# Conn_A.net
KiCad netlist of a schematic drawn in Altium Designer
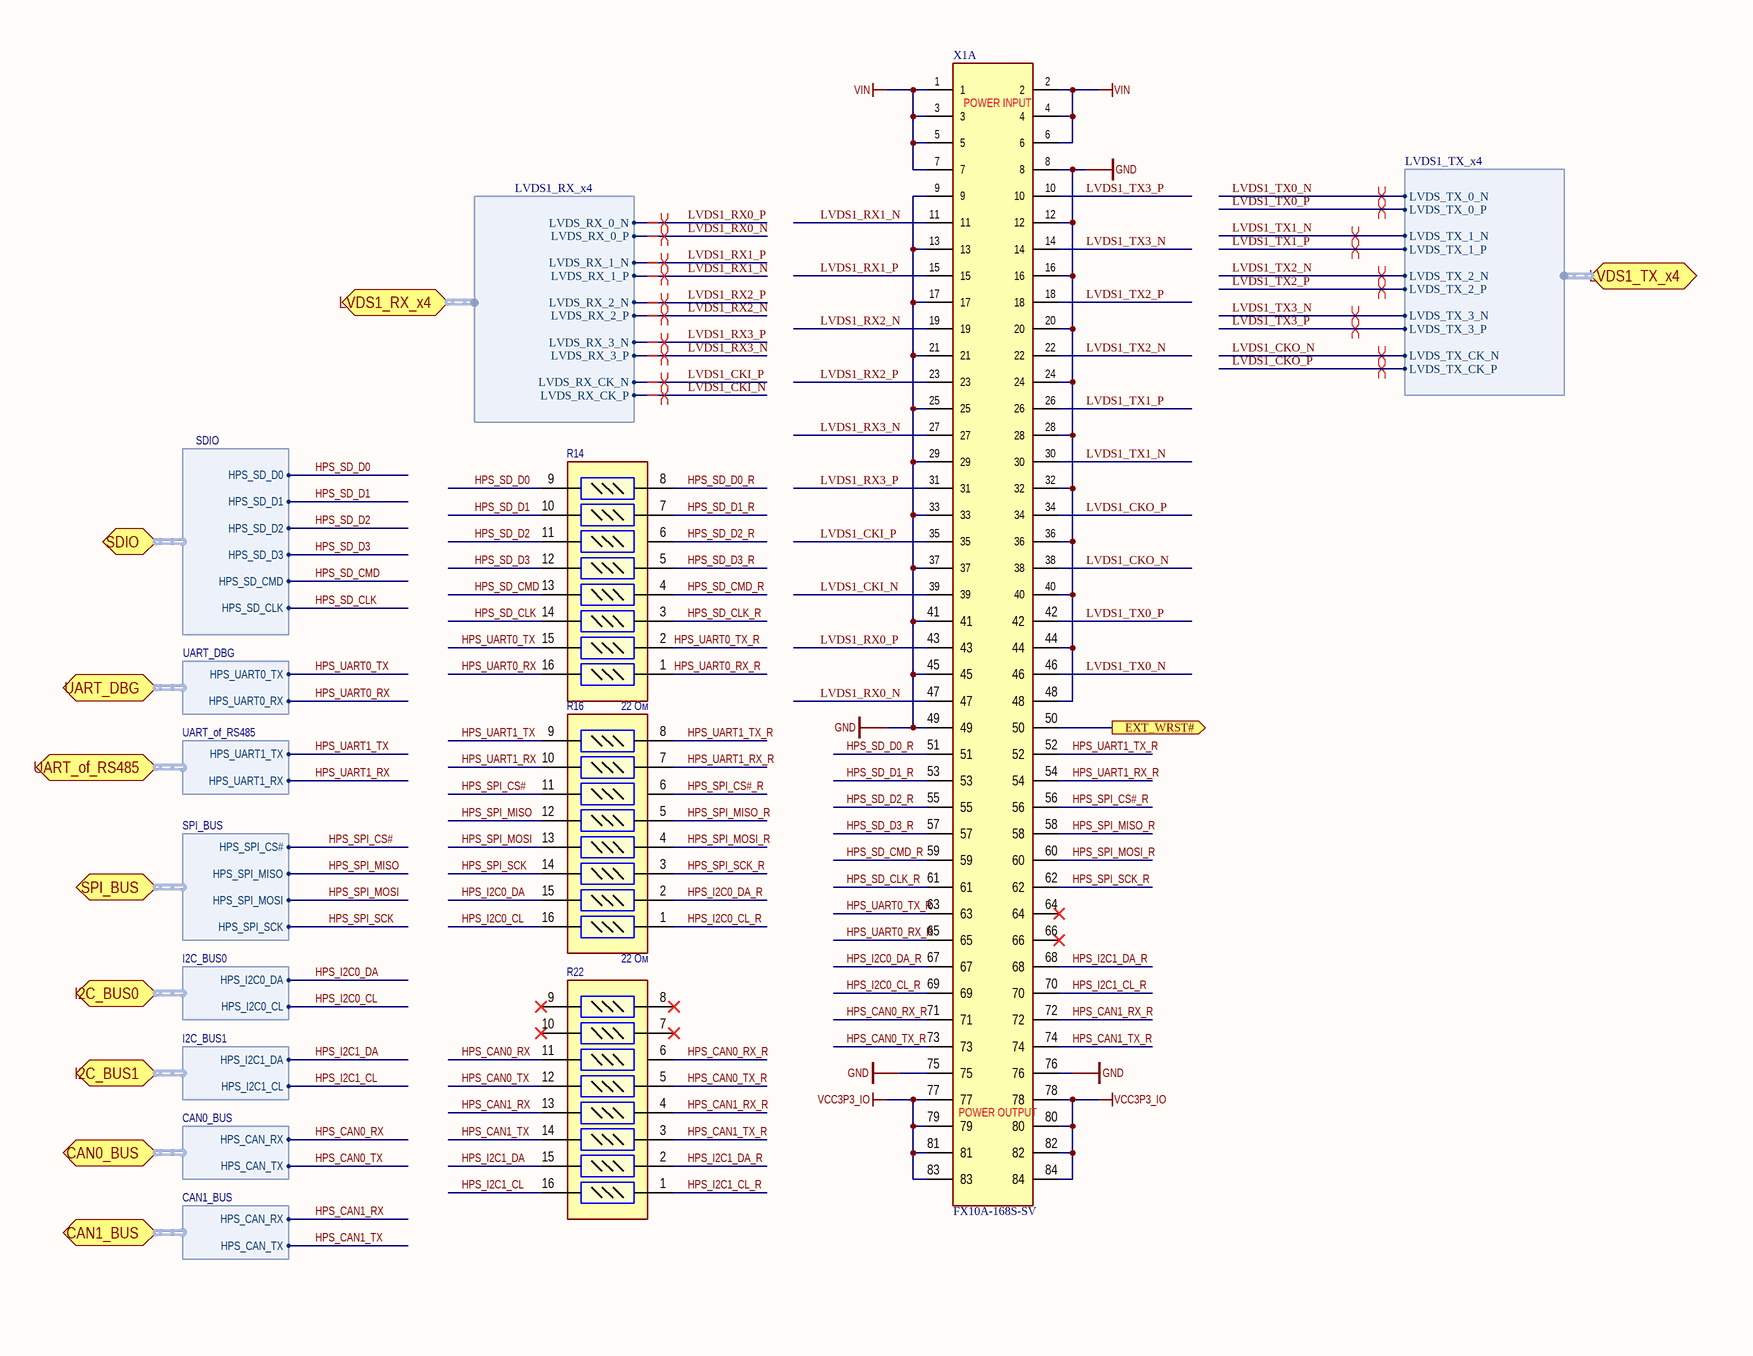
[diagram p0: Conn_A.SchDoc, left]
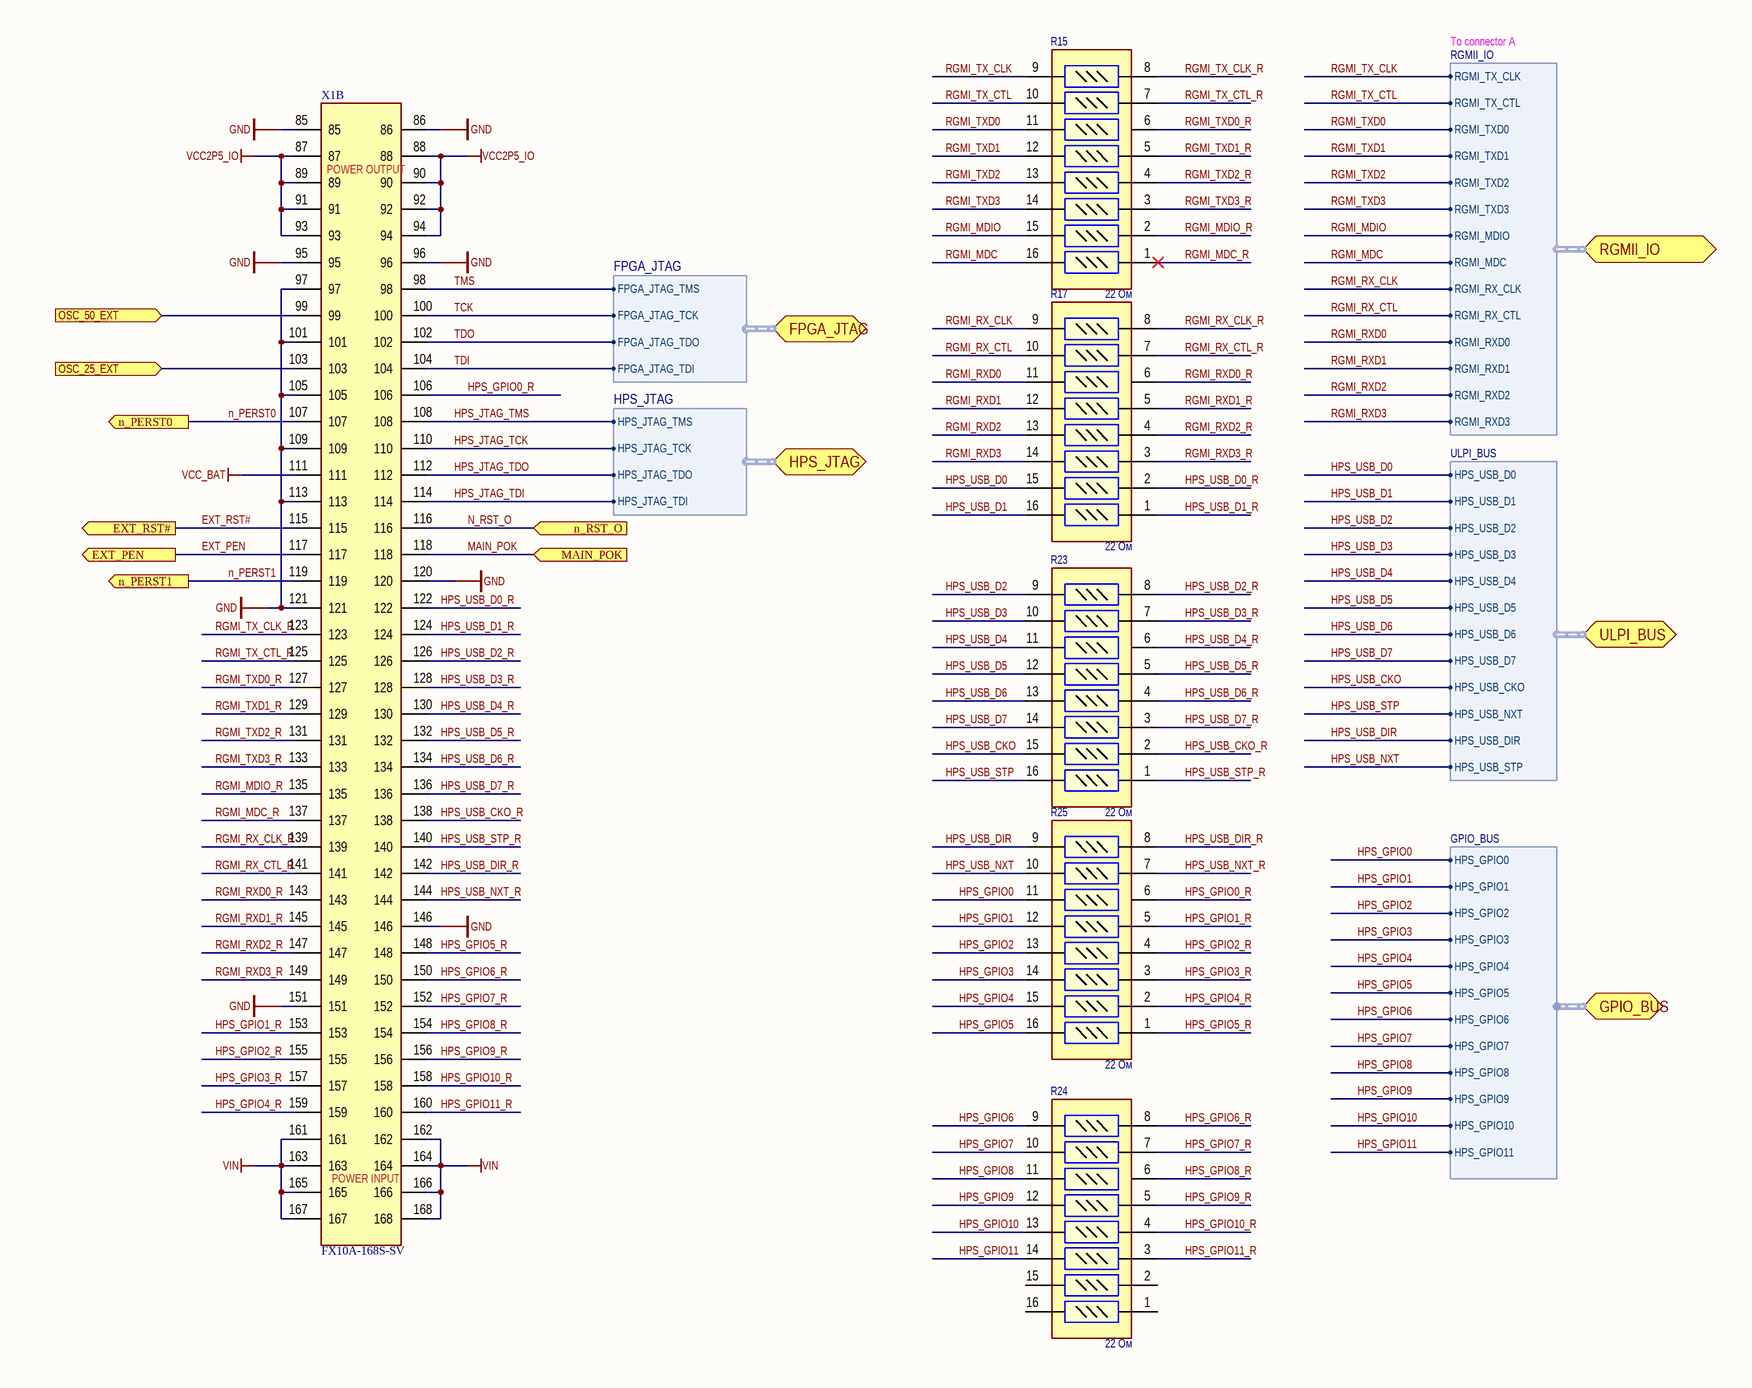
[diagram p1: Conn_A.SchDoc, right]

(export (version "E")
  (design (tool "Eeschema 10.0.6"))
  (components
    (comp (ref "R14")
      (value "22 Ом")
      (footprint "CAT16-J8")
      (description "Набор чип резисторов")
      (fields (field (name "Comment") "YC248-JR-07-22 Ом"))
      (libsource (lib "SD_IC") (part "YC248-JR-07-#"))
    )
    (comp (ref "R15")
      (value "22 Ом")
      (footprint "CAT16-J8")
      (description "Набор чип резисторов")
      (fields (field (name "Comment") "YC248-JR-07-22 Ом"))
      (libsource (lib "SD_IC") (part "YC248-JR-07-#"))
    )
    (comp (ref "R16")
      (value "22 Ом")
      (footprint "CAT16-J8")
      (description "Набор чип резисторов")
      (fields (field (name "Comment") "YC248-JR-07-22 Ом"))
      (libsource (lib "SD_IC") (part "YC248-JR-07-#"))
    )
    (comp (ref "R17")
      (value "22 Ом")
      (footprint "CAT16-J8")
      (description "Набор чип резисторов")
      (fields (field (name "Comment") "YC248-JR-07-22 Ом"))
      (libsource (lib "SD_IC") (part "YC248-JR-07-#"))
    )
    (comp (ref "R22")
      (value "YC248-JR-07-")
      (footprint "CAT16-J8")
      (description "Набор чип резисторов")
      (libsource (lib "SD_IC") (part "YC248-JR-07-#"))
    )
    (comp (ref "R23")
      (value "22 Ом")
      (footprint "CAT16-J8")
      (description "Набор чип резисторов")
      (fields (field (name "Comment") "YC248-JR-07-22 Ом"))
      (libsource (lib "SD_IC") (part "YC248-JR-07-#"))
    )
    (comp (ref "R24")
      (value "22 Ом")
      (footprint "CAT16-J8")
      (description "Набор чип резисторов")
      (fields (field (name "Comment") "YC248-JR-07-22 Ом"))
      (libsource (lib "SD_IC") (part "YC248-JR-07-#"))
    )
    (comp (ref "R25")
      (value "22 Ом")
      (footprint "CAT16-J8")
      (description "Набор чип резисторов")
      (fields (field (name "Comment") "YC248-JR-07-22 Ом"))
      (libsource (lib "SD_IC") (part "YC248-JR-07-#"))
    )
    (comp (ref "X1")
      (value "FX10A-168S-SV")
      (footprint "FX10A-168S-SV")
      (libsource (lib "SD_IC") (part "FX10A-168S-SV"))
    )
  )
  (nets
    (net (code "16") (name "/EXT_PEN") (class "Default")
      (node (ref "X1") (pin "117") (pinfunction "117_117") (pintype "passive"))
    )
    (net (code "17") (name "/EXT_RST#") (class "Default")
      (node (ref "X1") (pin "115") (pinfunction "115_115") (pintype "passive"))
    )
    (net (code "18") (name "/EXT_WRST#") (class "Default")
      (node (ref "X1") (pin "50") (pinfunction "50_50") (pintype "passive"))
    )
    (net (code "19") (name "/HPS_CAN0_RX") (class "Default")
      (node (ref "R22") (pin "11") (pintype "passive"))
    )
    (net (code "20") (name "/HPS_CAN0_RX_R") (class "Default")
      (node (ref "R22") (pin "6") (pintype "passive"))
      (node (ref "X1") (pin "71") (pinfunction "71_71") (pintype "passive"))
    )
    (net (code "21") (name "/HPS_CAN0_TX") (class "Default")
      (node (ref "R22") (pin "12") (pintype "passive"))
    )
    (net (code "22") (name "/HPS_CAN0_TX_R") (class "Default")
      (node (ref "R22") (pin "5") (pintype "passive"))
      (node (ref "X1") (pin "73") (pinfunction "73_73") (pintype "passive"))
    )
    (net (code "23") (name "/HPS_CAN1_RX") (class "Default")
      (node (ref "R22") (pin "13") (pintype "passive"))
    )
    (net (code "24") (name "/HPS_CAN1_RX_R") (class "Default")
      (node (ref "R22") (pin "4") (pintype "passive"))
      (node (ref "X1") (pin "72") (pinfunction "72_72") (pintype "passive"))
    )
    (net (code "25") (name "/HPS_CAN1_TX") (class "Default")
      (node (ref "R22") (pin "14") (pintype "passive"))
    )
    (net (code "26") (name "/HPS_CAN1_TX_R") (class "Default")
      (node (ref "R22") (pin "3") (pintype "passive"))
      (node (ref "X1") (pin "74") (pinfunction "74_74") (pintype "passive"))
    )
    (net (code "27") (name "/HPS_GPIO0") (class "Default") (node (ref "R25") (pin "11") (pintype "passive")))
    (net (code "28") (name "/HPS_GPIO0_R") (class "Default")
      (node (ref "R25") (pin "6") (pintype "passive"))
      (node (ref "X1") (pin "106") (pinfunction "106_106") (pintype "passive"))
    )
    (net (code "29") (name "/HPS_GPIO1") (class "Default") (node (ref "R25") (pin "12") (pintype "passive")))
    (net (code "30") (name "/HPS_GPIO1_R") (class "Default")
      (node (ref "R25") (pin "5") (pintype "passive"))
      (node (ref "X1") (pin "153") (pinfunction "153_153") (pintype "passive"))
    )
    (net (code "31") (name "/HPS_GPIO2") (class "Default") (node (ref "R25") (pin "13") (pintype "passive")))
    (net (code "32") (name "/HPS_GPIO2_R") (class "Default")
      (node (ref "R25") (pin "4") (pintype "passive"))
      (node (ref "X1") (pin "155") (pinfunction "155_155") (pintype "passive"))
    )
    (net (code "33") (name "/HPS_GPIO3") (class "Default") (node (ref "R25") (pin "14") (pintype "passive")))
    (net (code "34") (name "/HPS_GPIO3_R") (class "Default")
      (node (ref "R25") (pin "3") (pintype "passive"))
      (node (ref "X1") (pin "157") (pinfunction "157_157") (pintype "passive"))
    )
    (net (code "35") (name "/HPS_GPIO4") (class "Default") (node (ref "R25") (pin "15") (pintype "passive")))
    (net (code "36") (name "/HPS_GPIO4_R") (class "Default")
      (node (ref "R25") (pin "2") (pintype "passive"))
      (node (ref "X1") (pin "159") (pinfunction "159_159") (pintype "passive"))
    )
    (net (code "37") (name "/HPS_GPIO5") (class "Default") (node (ref "R25") (pin "16") (pintype "passive")))
    (net (code "38") (name "/HPS_GPIO5_R") (class "Default")
      (node (ref "R25") (pin "1") (pintype "passive"))
      (node (ref "X1") (pin "148") (pinfunction "148_148") (pintype "passive"))
    )
    (net (code "39") (name "/HPS_GPIO6") (class "Default") (node (ref "R24") (pin "9") (pintype "passive")))
    (net (code "40") (name "/HPS_GPIO6_R") (class "Default")
      (node (ref "R24") (pin "8") (pintype "passive"))
      (node (ref "X1") (pin "150") (pinfunction "150_150") (pintype "passive"))
    )
    (net (code "41") (name "/HPS_GPIO7") (class "Default") (node (ref "R24") (pin "10") (pintype "passive")))
    (net (code "42") (name "/HPS_GPIO7_R") (class "Default")
      (node (ref "R24") (pin "7") (pintype "passive"))
      (node (ref "X1") (pin "152") (pinfunction "152_152") (pintype "passive"))
    )
    (net (code "43") (name "/HPS_GPIO8") (class "Default") (node (ref "R24") (pin "11") (pintype "passive")))
    (net (code "44") (name "/HPS_GPIO8_R") (class "Default")
      (node (ref "R24") (pin "6") (pintype "passive"))
      (node (ref "X1") (pin "154") (pinfunction "154_154") (pintype "passive"))
    )
    (net (code "45") (name "/HPS_GPIO9") (class "Default") (node (ref "R24") (pin "12") (pintype "passive")))
    (net (code "46") (name "/HPS_GPIO9_R") (class "Default")
      (node (ref "R24") (pin "5") (pintype "passive"))
      (node (ref "X1") (pin "156") (pinfunction "156_156") (pintype "passive"))
    )
    (net (code "47") (name "/HPS_GPIO10") (class "Default") (node (ref "R24") (pin "13") (pintype "passive")))
    (net (code "48") (name "/HPS_GPIO10_R") (class "Default")
      (node (ref "R24") (pin "4") (pintype "passive"))
      (node (ref "X1") (pin "158") (pinfunction "158_158") (pintype "passive"))
    )
    (net (code "49") (name "/HPS_GPIO11") (class "Default") (node (ref "R24") (pin "14") (pintype "passive")))
    (net (code "50") (name "/HPS_GPIO11_R") (class "Default")
      (node (ref "R24") (pin "3") (pintype "passive"))
      (node (ref "X1") (pin "160") (pinfunction "160_160") (pintype "passive"))
    )
    (net (code "51") (name "/HPS_I2C0_CL") (class "Default")
      (node (ref "R16") (pin "16") (pintype "passive"))
    )
    (net (code "52") (name "/HPS_I2C0_CL_R") (class "Default")
      (node (ref "R16") (pin "1") (pintype "passive"))
      (node (ref "X1") (pin "69") (pinfunction "69_69") (pintype "passive"))
    )
    (net (code "53") (name "/HPS_I2C0_DA") (class "Default")
      (node (ref "R16") (pin "15") (pintype "passive"))
    )
    (net (code "54") (name "/HPS_I2C0_DA_R") (class "Default")
      (node (ref "R16") (pin "2") (pintype "passive"))
      (node (ref "X1") (pin "67") (pinfunction "67_67") (pintype "passive"))
    )
    (net (code "55") (name "/HPS_I2C1_CL") (class "Default")
      (node (ref "R22") (pin "16") (pintype "passive"))
    )
    (net (code "56") (name "/HPS_I2C1_CL_R") (class "Default")
      (node (ref "R22") (pin "1") (pintype "passive"))
      (node (ref "X1") (pin "70") (pinfunction "70_70") (pintype "passive"))
    )
    (net (code "57") (name "/HPS_I2C1_DA") (class "Default")
      (node (ref "R22") (pin "15") (pintype "passive"))
    )
    (net (code "58") (name "/HPS_I2C1_DA_R") (class "Default")
      (node (ref "R22") (pin "2") (pintype "passive"))
      (node (ref "X1") (pin "68") (pinfunction "68_68") (pintype "passive"))
    )
    (net (code "59") (name "/HPS_JTAG_TCK") (class "Default")
      (node (ref "X1") (pin "110") (pinfunction "110_110") (pintype "passive"))
    )
    (net (code "60") (name "/HPS_JTAG_TDI") (class "Default")
      (node (ref "X1") (pin "114") (pinfunction "114_114") (pintype "passive"))
    )
    (net (code "61") (name "/HPS_JTAG_TDO") (class "Default")
      (node (ref "X1") (pin "112") (pinfunction "112_112") (pintype "passive"))
    )
    (net (code "62") (name "/HPS_JTAG_TMS") (class "Default")
      (node (ref "X1") (pin "108") (pinfunction "108_108") (pintype "passive"))
    )
    (net (code "63") (name "/HPS_SD_CLK") (class "Default") (node (ref "R14") (pin "14") (pintype "passive")))
    (net (code "64") (name "/HPS_SD_CLK_R") (class "Default")
      (node (ref "R14") (pin "3") (pintype "passive"))
      (node (ref "X1") (pin "61") (pinfunction "61_61") (pintype "passive"))
    )
    (net (code "65") (name "/HPS_SD_CMD") (class "Default") (node (ref "R14") (pin "13") (pintype "passive")))
    (net (code "66") (name "/HPS_SD_CMD_R") (class "Default")
      (node (ref "R14") (pin "4") (pintype "passive"))
      (node (ref "X1") (pin "59") (pinfunction "59_59") (pintype "passive"))
    )
    (net (code "67") (name "/HPS_SD_D0") (class "Default") (node (ref "R14") (pin "9") (pintype "passive")))
    (net (code "68") (name "/HPS_SD_D0_R") (class "Default")
      (node (ref "R14") (pin "8") (pintype "passive"))
      (node (ref "X1") (pin "51") (pinfunction "51_51") (pintype "passive"))
    )
    (net (code "69") (name "/HPS_SD_D1") (class "Default") (node (ref "R14") (pin "10") (pintype "passive")))
    (net (code "70") (name "/HPS_SD_D1_R") (class "Default")
      (node (ref "R14") (pin "7") (pintype "passive"))
      (node (ref "X1") (pin "53") (pinfunction "53_53") (pintype "passive"))
    )
    (net (code "71") (name "/HPS_SD_D2") (class "Default") (node (ref "R14") (pin "11") (pintype "passive")))
    (net (code "72") (name "/HPS_SD_D2_R") (class "Default")
      (node (ref "R14") (pin "6") (pintype "passive"))
      (node (ref "X1") (pin "55") (pinfunction "55_55") (pintype "passive"))
    )
    (net (code "73") (name "/HPS_SD_D3") (class "Default") (node (ref "R14") (pin "12") (pintype "passive")))
    (net (code "74") (name "/HPS_SD_D3_R") (class "Default")
      (node (ref "R14") (pin "5") (pintype "passive"))
      (node (ref "X1") (pin "57") (pinfunction "57_57") (pintype "passive"))
    )
    (net (code "75") (name "/HPS_SPI_CS#") (class "Default")
      (node (ref "R16") (pin "11") (pintype "passive"))
    )
    (net (code "76") (name "/HPS_SPI_CS#_R") (class "Default")
      (node (ref "R16") (pin "6") (pintype "passive"))
      (node (ref "X1") (pin "56") (pinfunction "56_56") (pintype "passive"))
    )
    (net (code "77") (name "/HPS_SPI_MISO") (class "Default")
      (node (ref "R16") (pin "12") (pintype "passive"))
    )
    (net (code "78") (name "/HPS_SPI_MISO_R") (class "Default")
      (node (ref "R16") (pin "5") (pintype "passive"))
      (node (ref "X1") (pin "58") (pinfunction "58_58") (pintype "passive"))
    )
    (net (code "79") (name "/HPS_SPI_MOSI") (class "Default")
      (node (ref "R16") (pin "13") (pintype "passive"))
    )
    (net (code "80") (name "/HPS_SPI_MOSI_R") (class "Default")
      (node (ref "R16") (pin "4") (pintype "passive"))
      (node (ref "X1") (pin "60") (pinfunction "60_60") (pintype "passive"))
    )
    (net (code "81") (name "/HPS_SPI_SCK") (class "Default")
      (node (ref "R16") (pin "14") (pintype "passive"))
    )
    (net (code "82") (name "/HPS_SPI_SCK_R") (class "Default")
      (node (ref "R16") (pin "3") (pintype "passive"))
      (node (ref "X1") (pin "62") (pinfunction "62_62") (pintype "passive"))
    )
    (net (code "83") (name "/HPS_UART0_RX") (class "Default")
      (node (ref "R14") (pin "16") (pintype "passive"))
    )
    (net (code "84") (name "/HPS_UART0_RX_R") (class "Default")
      (node (ref "R14") (pin "1") (pintype "passive"))
      (node (ref "X1") (pin "65") (pinfunction "65_65") (pintype "passive"))
    )
    (net (code "85") (name "/HPS_UART0_TX") (class "Default")
      (node (ref "R14") (pin "15") (pintype "passive"))
    )
    (net (code "86") (name "/HPS_UART0_TX_R") (class "Default")
      (node (ref "R14") (pin "2") (pintype "passive"))
      (node (ref "X1") (pin "63") (pinfunction "63_63") (pintype "passive"))
    )
    (net (code "87") (name "/HPS_UART1_RX") (class "Default")
      (node (ref "R16") (pin "10") (pintype "passive"))
    )
    (net (code "88") (name "/HPS_UART1_RX_R") (class "Default")
      (node (ref "R16") (pin "7") (pintype "passive"))
      (node (ref "X1") (pin "54") (pinfunction "54_54") (pintype "passive"))
    )
    (net (code "89") (name "/HPS_UART1_TX") (class "Default")
      (node (ref "R16") (pin "9") (pintype "passive"))
    )
    (net (code "90") (name "/HPS_UART1_TX_R") (class "Default")
      (node (ref "R16") (pin "8") (pintype "passive"))
      (node (ref "X1") (pin "52") (pinfunction "52_52") (pintype "passive"))
    )
    (net (code "91") (name "/HPS_USB_CKO") (class "Default")
      (node (ref "R23") (pin "15") (pintype "passive"))
    )
    (net (code "92") (name "/HPS_USB_CKO_R") (class "Default")
      (node (ref "R23") (pin "2") (pintype "passive"))
      (node (ref "X1") (pin "138") (pinfunction "138_138") (pintype "passive"))
    )
    (net (code "93") (name "/HPS_USB_D0") (class "Default") (node (ref "R17") (pin "15") (pintype "passive")))
    (net (code "94") (name "/HPS_USB_D0_R") (class "Default")
      (node (ref "R17") (pin "2") (pintype "passive"))
      (node (ref "X1") (pin "122") (pinfunction "122_122") (pintype "passive"))
    )
    (net (code "95") (name "/HPS_USB_D1") (class "Default") (node (ref "R17") (pin "16") (pintype "passive")))
    (net (code "96") (name "/HPS_USB_D1_R") (class "Default")
      (node (ref "R17") (pin "1") (pintype "passive"))
      (node (ref "X1") (pin "124") (pinfunction "124_124") (pintype "passive"))
    )
    (net (code "97") (name "/HPS_USB_D2") (class "Default") (node (ref "R23") (pin "9") (pintype "passive")))
    (net (code "98") (name "/HPS_USB_D2_R") (class "Default")
      (node (ref "R23") (pin "8") (pintype "passive"))
      (node (ref "X1") (pin "126") (pinfunction "126_126") (pintype "passive"))
    )
    (net (code "99") (name "/HPS_USB_D3") (class "Default") (node (ref "R23") (pin "10") (pintype "passive")))
    (net (code "100") (name "/HPS_USB_D3_R") (class "Default")
      (node (ref "R23") (pin "7") (pintype "passive"))
      (node (ref "X1") (pin "128") (pinfunction "128_128") (pintype "passive"))
    )
    (net (code "101") (name "/HPS_USB_D4") (class "Default")
      (node (ref "R23") (pin "11") (pintype "passive"))
    )
    (net (code "102") (name "/HPS_USB_D4_R") (class "Default")
      (node (ref "R23") (pin "6") (pintype "passive"))
      (node (ref "X1") (pin "130") (pinfunction "130_130") (pintype "passive"))
    )
    (net (code "103") (name "/HPS_USB_D5") (class "Default")
      (node (ref "R23") (pin "12") (pintype "passive"))
    )
    (net (code "104") (name "/HPS_USB_D5_R") (class "Default")
      (node (ref "R23") (pin "5") (pintype "passive"))
      (node (ref "X1") (pin "132") (pinfunction "132_132") (pintype "passive"))
    )
    (net (code "105") (name "/HPS_USB_D6") (class "Default")
      (node (ref "R23") (pin "13") (pintype "passive"))
    )
    (net (code "106") (name "/HPS_USB_D6_R") (class "Default")
      (node (ref "R23") (pin "4") (pintype "passive"))
      (node (ref "X1") (pin "134") (pinfunction "134_134") (pintype "passive"))
    )
    (net (code "107") (name "/HPS_USB_D7") (class "Default")
      (node (ref "R23") (pin "14") (pintype "passive"))
    )
    (net (code "108") (name "/HPS_USB_D7_R") (class "Default")
      (node (ref "R23") (pin "3") (pintype "passive"))
      (node (ref "X1") (pin "136") (pinfunction "136_136") (pintype "passive"))
    )
    (net (code "109") (name "/HPS_USB_DIR") (class "Default")
      (node (ref "R25") (pin "9") (pintype "passive"))
    )
    (net (code "110") (name "/HPS_USB_DIR_R") (class "Default")
      (node (ref "R25") (pin "8") (pintype "passive"))
      (node (ref "X1") (pin "142") (pinfunction "142_142") (pintype "passive"))
    )
    (net (code "111") (name "/HPS_USB_NXT") (class "Default")
      (node (ref "R25") (pin "10") (pintype "passive"))
    )
    (net (code "112") (name "/HPS_USB_NXT_R") (class "Default")
      (node (ref "R25") (pin "7") (pintype "passive"))
      (node (ref "X1") (pin "144") (pinfunction "144_144") (pintype "passive"))
    )
    (net (code "113") (name "/HPS_USB_STP") (class "Default")
      (node (ref "R23") (pin "16") (pintype "passive"))
    )
    (net (code "114") (name "/HPS_USB_STP_R") (class "Default")
      (node (ref "R23") (pin "1") (pintype "passive"))
      (node (ref "X1") (pin "140") (pinfunction "140_140") (pintype "passive"))
    )
    (net (code "115") (name "/LVDS1_CKI_N") (class "Default")
      (node (ref "X1") (pin "39") (pinfunction "39_39") (pintype "passive"))
    )
    (net (code "116") (name "/LVDS1_CKI_P") (class "Default")
      (node (ref "X1") (pin "35") (pinfunction "35_35") (pintype "passive"))
    )
    (net (code "117") (name "/LVDS1_CKO_N") (class "Default")
      (node (ref "X1") (pin "38") (pinfunction "38_38") (pintype "passive"))
    )
    (net (code "118") (name "/LVDS1_CKO_P") (class "Default")
      (node (ref "X1") (pin "34") (pinfunction "34_34") (pintype "passive"))
    )
    (net (code "119") (name "/LVDS1_RX0_N") (class "Default")
      (node (ref "X1") (pin "47") (pinfunction "47_47") (pintype "passive"))
    )
    (net (code "120") (name "/LVDS1_RX0_P") (class "Default")
      (node (ref "X1") (pin "43") (pinfunction "43_43") (pintype "passive"))
    )
    (net (code "121") (name "/LVDS1_RX1_N") (class "Default")
      (node (ref "X1") (pin "11") (pinfunction "11_11") (pintype "passive"))
    )
    (net (code "122") (name "/LVDS1_RX1_P") (class "Default")
      (node (ref "X1") (pin "15") (pinfunction "15_15") (pintype "passive"))
    )
    (net (code "123") (name "/LVDS1_RX2_N") (class "Default")
      (node (ref "X1") (pin "19") (pinfunction "19_19") (pintype "passive"))
    )
    (net (code "124") (name "/LVDS1_RX2_P") (class "Default")
      (node (ref "X1") (pin "23") (pinfunction "23_23") (pintype "passive"))
    )
    (net (code "125") (name "/LVDS1_RX3_N") (class "Default")
      (node (ref "X1") (pin "27") (pinfunction "27_27") (pintype "passive"))
    )
    (net (code "126") (name "/LVDS1_RX3_P") (class "Default")
      (node (ref "X1") (pin "31") (pinfunction "31_31") (pintype "passive"))
    )
    (net (code "127") (name "/LVDS1_TX0_N") (class "Default")
      (node (ref "X1") (pin "46") (pinfunction "46_46") (pintype "passive"))
    )
    (net (code "128") (name "/LVDS1_TX0_P") (class "Default")
      (node (ref "X1") (pin "42") (pinfunction "42_42") (pintype "passive"))
    )
    (net (code "129") (name "/LVDS1_TX1_N") (class "Default")
      (node (ref "X1") (pin "30") (pinfunction "30_30") (pintype "passive"))
    )
    (net (code "130") (name "/LVDS1_TX1_P") (class "Default")
      (node (ref "X1") (pin "26") (pinfunction "26_26") (pintype "passive"))
    )
    (net (code "131") (name "/LVDS1_TX2_N") (class "Default")
      (node (ref "X1") (pin "22") (pinfunction "22_22") (pintype "passive"))
    )
    (net (code "132") (name "/LVDS1_TX2_P") (class "Default")
      (node (ref "X1") (pin "18") (pinfunction "18_18") (pintype "passive"))
    )
    (net (code "133") (name "/LVDS1_TX3_N") (class "Default")
      (node (ref "X1") (pin "14") (pinfunction "14_14") (pintype "passive"))
    )
    (net (code "134") (name "/LVDS1_TX3_P") (class "Default")
      (node (ref "X1") (pin "10") (pinfunction "10_10") (pintype "passive"))
    )
    (net (code "135") (name "/MAIN_POK") (class "Default")
      (node (ref "X1") (pin "118") (pinfunction "118_118") (pintype "passive"))
    )
    (net (code "136") (name "/N_RST_O") (class "Default")
      (node (ref "X1") (pin "116") (pinfunction "116_116") (pintype "passive"))
    )
    (net (code "137") (name "/OSC_25_EXT") (class "Default")
      (node (ref "X1") (pin "103") (pinfunction "103_103") (pintype "passive"))
    )
    (net (code "138") (name "/OSC_50_EXT") (class "Default")
      (node (ref "X1") (pin "99") (pinfunction "99_99") (pintype "passive"))
    )
    (net (code "139") (name "/RGMI_MDC") (class "Default") (node (ref "R15") (pin "16") (pintype "passive")))
    (net (code "140") (name "/RGMI_MDC_R") (class "Default")
      (node (ref "R15") (pin "1") (pintype "passive"))
      (node (ref "X1") (pin "137") (pinfunction "137_137") (pintype "passive"))
    )
    (net (code "141") (name "/RGMI_MDIO") (class "Default") (node (ref "R15") (pin "15") (pintype "passive")))
    (net (code "142") (name "/RGMI_MDIO_R") (class "Default")
      (node (ref "R15") (pin "2") (pintype "passive"))
      (node (ref "X1") (pin "135") (pinfunction "135_135") (pintype "passive"))
    )
    (net (code "143") (name "/RGMI_RXD0") (class "Default") (node (ref "R17") (pin "11") (pintype "passive")))
    (net (code "144") (name "/RGMI_RXD0_R") (class "Default")
      (node (ref "R17") (pin "6") (pintype "passive"))
      (node (ref "X1") (pin "143") (pinfunction "143_143") (pintype "passive"))
    )
    (net (code "145") (name "/RGMI_RXD1") (class "Default") (node (ref "R17") (pin "12") (pintype "passive")))
    (net (code "146") (name "/RGMI_RXD1_R") (class "Default")
      (node (ref "R17") (pin "5") (pintype "passive"))
      (node (ref "X1") (pin "145") (pinfunction "145_145") (pintype "passive"))
    )
    (net (code "147") (name "/RGMI_RXD2") (class "Default") (node (ref "R17") (pin "13") (pintype "passive")))
    (net (code "148") (name "/RGMI_RXD2_R") (class "Default")
      (node (ref "R17") (pin "4") (pintype "passive"))
      (node (ref "X1") (pin "147") (pinfunction "147_147") (pintype "passive"))
    )
    (net (code "149") (name "/RGMI_RXD3") (class "Default") (node (ref "R17") (pin "14") (pintype "passive")))
    (net (code "150") (name "/RGMI_RXD3_R") (class "Default")
      (node (ref "R17") (pin "3") (pintype "passive"))
      (node (ref "X1") (pin "149") (pinfunction "149_149") (pintype "passive"))
    )
    (net (code "151") (name "/RGMI_RX_CLK") (class "Default")
      (node (ref "R17") (pin "9") (pintype "passive"))
    )
    (net (code "152") (name "/RGMI_RX_CLK_R") (class "Default")
      (node (ref "R17") (pin "8") (pintype "passive"))
      (node (ref "X1") (pin "139") (pinfunction "139_139") (pintype "passive"))
    )
    (net (code "153") (name "/RGMI_RX_CTL") (class "Default")
      (node (ref "R17") (pin "10") (pintype "passive"))
    )
    (net (code "154") (name "/RGMI_RX_CTL_R") (class "Default")
      (node (ref "R17") (pin "7") (pintype "passive"))
      (node (ref "X1") (pin "141") (pinfunction "141_141") (pintype "passive"))
    )
    (net (code "155") (name "/RGMI_TXD0") (class "Default") (node (ref "R15") (pin "11") (pintype "passive")))
    (net (code "156") (name "/RGMI_TXD0_R") (class "Default")
      (node (ref "R15") (pin "6") (pintype "passive"))
      (node (ref "X1") (pin "127") (pinfunction "127_127") (pintype "passive"))
    )
    (net (code "157") (name "/RGMI_TXD1") (class "Default") (node (ref "R15") (pin "12") (pintype "passive")))
    (net (code "158") (name "/RGMI_TXD1_R") (class "Default")
      (node (ref "R15") (pin "5") (pintype "passive"))
      (node (ref "X1") (pin "129") (pinfunction "129_129") (pintype "passive"))
    )
    (net (code "159") (name "/RGMI_TXD2") (class "Default") (node (ref "R15") (pin "13") (pintype "passive")))
    (net (code "160") (name "/RGMI_TXD2_R") (class "Default")
      (node (ref "R15") (pin "4") (pintype "passive"))
      (node (ref "X1") (pin "131") (pinfunction "131_131") (pintype "passive"))
    )
    (net (code "161") (name "/RGMI_TXD3") (class "Default") (node (ref "R15") (pin "14") (pintype "passive")))
    (net (code "162") (name "/RGMI_TXD3_R") (class "Default")
      (node (ref "R15") (pin "3") (pintype "passive"))
      (node (ref "X1") (pin "133") (pinfunction "133_133") (pintype "passive"))
    )
    (net (code "163") (name "/RGMI_TX_CLK") (class "Default")
      (node (ref "R15") (pin "9") (pintype "passive"))
    )
    (net (code "164") (name "/RGMI_TX_CLK_R") (class "Default")
      (node (ref "R15") (pin "8") (pintype "passive"))
      (node (ref "X1") (pin "123") (pinfunction "123_123") (pintype "passive"))
    )
    (net (code "165") (name "/RGMI_TX_CTL") (class "Default")
      (node (ref "R15") (pin "10") (pintype "passive"))
    )
    (net (code "166") (name "/RGMI_TX_CTL_R") (class "Default")
      (node (ref "R15") (pin "7") (pintype "passive"))
      (node (ref "X1") (pin "125") (pinfunction "125_125") (pintype "passive"))
    )
    (net (code "167") (name "/TCK") (class "Default")
      (node (ref "X1") (pin "100") (pinfunction "100_100") (pintype "passive"))
    )
    (net (code "168") (name "/TDI") (class "Default")
      (node (ref "X1") (pin "104") (pinfunction "104_104") (pintype "passive"))
    )
    (net (code "169") (name "/TDO") (class "Default")
      (node (ref "X1") (pin "102") (pinfunction "102_102") (pintype "passive"))
    )
    (net (code "170") (name "/TMS") (class "Default")
      (node (ref "X1") (pin "98") (pinfunction "98_98") (pintype "passive"))
    )
    (net (code "171") (name "/n_PERST0") (class "Default")
      (node (ref "X1") (pin "107") (pinfunction "107_107") (pintype "passive"))
    )
    (net (code "172") (name "/n_PERST1") (class "Default")
      (node (ref "X1") (pin "119") (pinfunction "119_119") (pintype "passive"))
    )
    (net (code "188") (name "GND") (class "Default")
      (node (ref "X1") (pin "101") (pinfunction "101_101") (pintype "passive"))
      (node (ref "X1") (pin "105") (pinfunction "105_105") (pintype "passive"))
      (node (ref "X1") (pin "109") (pinfunction "109_109") (pintype "passive"))
      (node (ref "X1") (pin "113") (pinfunction "113_113") (pintype "passive"))
      (node (ref "X1") (pin "12") (pinfunction "12_12") (pintype "passive"))
      (node (ref "X1") (pin "120") (pinfunction "120_120") (pintype "passive"))
      (node (ref "X1") (pin "121") (pinfunction "121_121") (pintype "passive"))
      (node (ref "X1") (pin "13") (pinfunction "13_13") (pintype "passive"))
      (node (ref "X1") (pin "146") (pinfunction "146_146") (pintype "passive"))
      (node (ref "X1") (pin "151") (pinfunction "151_151") (pintype "passive"))
      (node (ref "X1") (pin "16") (pinfunction "16_16") (pintype "passive"))
      (node (ref "X1") (pin "17") (pinfunction "17_17") (pintype "passive"))
      (node (ref "X1") (pin "20") (pinfunction "20_20") (pintype "passive"))
      (node (ref "X1") (pin "21") (pinfunction "21_21") (pintype "passive"))
      (node (ref "X1") (pin "24") (pinfunction "24_24") (pintype "passive"))
      (node (ref "X1") (pin "25") (pinfunction "25_25") (pintype "passive"))
      (node (ref "X1") (pin "28") (pinfunction "28_28") (pintype "passive"))
      (node (ref "X1") (pin "29") (pinfunction "29_29") (pintype "passive"))
      (node (ref "X1") (pin "32") (pinfunction "32_32") (pintype "passive"))
      (node (ref "X1") (pin "33") (pinfunction "33_33") (pintype "passive"))
      (node (ref "X1") (pin "36") (pinfunction "36_36") (pintype "passive"))
      (node (ref "X1") (pin "37") (pinfunction "37_37") (pintype "passive"))
      (node (ref "X1") (pin "40") (pinfunction "40_40") (pintype "passive"))
      (node (ref "X1") (pin "41") (pinfunction "41_41") (pintype "passive"))
      (node (ref "X1") (pin "44") (pinfunction "44_44") (pintype "passive"))
      (node (ref "X1") (pin "45") (pinfunction "45_45") (pintype "passive"))
      (node (ref "X1") (pin "48") (pinfunction "48_48") (pintype "passive"))
      (node (ref "X1") (pin "49") (pinfunction "49_49") (pintype "passive"))
      (node (ref "X1") (pin "75") (pinfunction "75_75") (pintype "passive"))
      (node (ref "X1") (pin "76") (pinfunction "76_76") (pintype "passive"))
      (node (ref "X1") (pin "8") (pinfunction "8_8") (pintype "passive"))
      (node (ref "X1") (pin "85") (pinfunction "85_85") (pintype "passive"))
      (node (ref "X1") (pin "86") (pinfunction "86_86") (pintype "passive"))
      (node (ref "X1") (pin "9") (pinfunction "9_9") (pintype "passive"))
      (node (ref "X1") (pin "95") (pinfunction "95_95") (pintype "passive"))
      (node (ref "X1") (pin "96") (pinfunction "96_96") (pintype "passive"))
      (node (ref "X1") (pin "97") (pinfunction "97_97") (pintype "passive"))
    )
    (net (code "189") (name "VCC2P5_IO") (class "Default")
      (node (ref "X1") (pin "87") (pinfunction "87_87") (pintype "passive"))
      (node (ref "X1") (pin "88") (pinfunction "88_88") (pintype "passive"))
      (node (ref "X1") (pin "89") (pinfunction "89_89") (pintype "passive"))
      (node (ref "X1") (pin "90") (pinfunction "90_90") (pintype "passive"))
      (node (ref "X1") (pin "91") (pinfunction "91_91") (pintype "passive"))
      (node (ref "X1") (pin "92") (pinfunction "92_92") (pintype "passive"))
      (node (ref "X1") (pin "93") (pinfunction "93_93") (pintype "passive"))
      (node (ref "X1") (pin "94") (pinfunction "94_94") (pintype "passive"))
    )
    (net (code "190") (name "VCC3P3_IO") (class "Default")
      (node (ref "X1") (pin "77") (pinfunction "77_77") (pintype "passive"))
      (node (ref "X1") (pin "78") (pinfunction "78_78") (pintype "passive"))
      (node (ref "X1") (pin "79") (pinfunction "79_79") (pintype "passive"))
      (node (ref "X1") (pin "80") (pinfunction "80_80") (pintype "passive"))
      (node (ref "X1") (pin "81") (pinfunction "81_81") (pintype "passive"))
      (node (ref "X1") (pin "82") (pinfunction "82_82") (pintype "passive"))
      (node (ref "X1") (pin "83") (pinfunction "83_83") (pintype "passive"))
      (node (ref "X1") (pin "84") (pinfunction "84_84") (pintype "passive"))
    )
    (net (code "191") (name "VCC_BAT") (class "Default")
      (node (ref "X1") (pin "111") (pinfunction "111_111") (pintype "passive"))
    )
    (net (code "192") (name "VIN") (class "Default")
      (node (ref "X1") (pin "1") (pinfunction "1_1") (pintype "passive"))
      (node (ref "X1") (pin "161") (pinfunction "161_161") (pintype "passive"))
      (node (ref "X1") (pin "162") (pinfunction "162_162") (pintype "passive"))
      (node (ref "X1") (pin "163") (pinfunction "163_163") (pintype "passive"))
      (node (ref "X1") (pin "164") (pinfunction "164_164") (pintype "passive"))
      (node (ref "X1") (pin "165") (pinfunction "165_165") (pintype "passive"))
      (node (ref "X1") (pin "166") (pinfunction "166_166") (pintype "passive"))
      (node (ref "X1") (pin "167") (pinfunction "167_167") (pintype "passive"))
      (node (ref "X1") (pin "168") (pinfunction "168_168") (pintype "passive"))
      (node (ref "X1") (pin "2") (pinfunction "2_2") (pintype "passive"))
      (node (ref "X1") (pin "3") (pinfunction "3_3") (pintype "passive"))
      (node (ref "X1") (pin "4") (pinfunction "4_4") (pintype "passive"))
      (node (ref "X1") (pin "5") (pinfunction "5_5") (pintype "passive"))
      (node (ref "X1") (pin "6") (pinfunction "6_6") (pintype "passive"))
      (node (ref "X1") (pin "7") (pinfunction "7_7") (pintype "passive"))
    )
    (net (code "193") (name "unconnected-(R22-Pad7)") (class "Default")
      (node (ref "R22") (pin "7") (pintype "passive+no_connect"))
    )
    (net (code "194") (name "unconnected-(R22-Pad8)") (class "Default")
      (node (ref "R22") (pin "8") (pintype "passive+no_connect"))
    )
    (net (code "195") (name "unconnected-(R22-Pad9)") (class "Default")
      (node (ref "R22") (pin "9") (pintype "passive+no_connect"))
    )
    (net (code "196") (name "unconnected-(R22-Pad10)") (class "Default")
      (node (ref "R22") (pin "10") (pintype "passive+no_connect"))
    )
    (net (code "197") (name "unconnected-(R24-Pad1)") (class "Default")
      (node (ref "R24") (pin "1") (pintype "passive"))
    )
    (net (code "198") (name "unconnected-(R24-Pad2)") (class "Default")
      (node (ref "R24") (pin "2") (pintype "passive"))
    )
    (net (code "199") (name "unconnected-(R24-Pad15)") (class "Default")
      (node (ref "R24") (pin "15") (pintype "passive"))
    )
    (net (code "200") (name "unconnected-(R24-Pad16)") (class "Default")
      (node (ref "R24") (pin "16") (pintype "passive"))
    )
    (net (code "201") (name "unconnected-(X1-Pad64)") (class "Default")
      (node (ref "X1") (pin "64") (pinfunction "64_64") (pintype "passive+no_connect"))
    )
    (net (code "202") (name "unconnected-(X1-Pad66)") (class "Default")
      (node (ref "X1") (pin "66") (pinfunction "66_66") (pintype "passive+no_connect"))
    )
  )
)
